# MO_v1.net
KiCad netlist of a schematic drawn in EAGLE
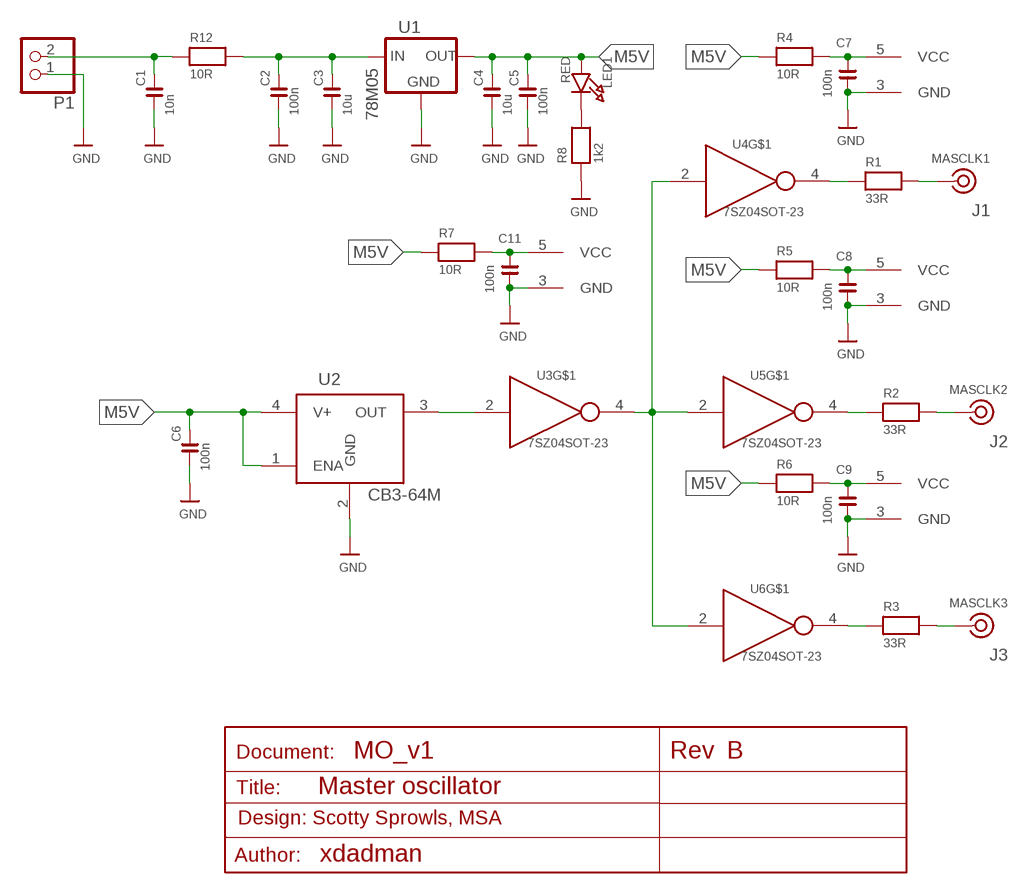
[diagram p0: schematic, sheet 1]

(export (version "E")
  (design (tool "Eeschema 10.0.6"))
  (components
    (comp (ref "C1")
      (value "10n")
      (footprint "eagle-import:C0805")
      (libsource (lib "eagle-import") (part "C080510N"))
    )
    (comp (ref "C2")
      (value "100n")
      (footprint "eagle-import:C0805")
      (libsource (lib "eagle-import") (part "C0805100N"))
    )
    (comp (ref "C3")
      (value "10u")
      (footprint "eagle-import:C1206")
      (libsource (lib "eagle-import") (part "CC120610U"))
    )
    (comp (ref "C4")
      (value "10u")
      (footprint "eagle-import:C1206")
      (libsource (lib "eagle-import") (part "CC120610U"))
    )
    (comp (ref "C5")
      (value "100n")
      (footprint "eagle-import:C0805")
      (libsource (lib "eagle-import") (part "C0805100N"))
    )
    (comp (ref "C6")
      (value "100n")
      (footprint "eagle-import:C0805")
      (libsource (lib "eagle-import") (part "C0805100N"))
    )
    (comp (ref "C7")
      (value "100n")
      (footprint "eagle-import:C0805")
      (libsource (lib "eagle-import") (part "C0805100N"))
    )
    (comp (ref "C8")
      (value "100n")
      (footprint "eagle-import:C0805")
      (libsource (lib "eagle-import") (part "C0805100N"))
    )
    (comp (ref "C9")
      (value "100n")
      (footprint "eagle-import:C0805")
      (libsource (lib "eagle-import") (part "C0805100N"))
    )
    (comp (ref "C11")
      (value "100n")
      (footprint "eagle-import:C0805")
      (libsource (lib "eagle-import") (part "C0805100N"))
    )
    (comp (ref "J1")
      (value "MASCLK1")
      (footprint "eagle-import:SLIM_COAX_PAD")
      (libsource (lib "eagle-import") (part "COAX"))
    )
    (comp (ref "J2")
      (value "MASCLK2")
      (footprint "eagle-import:SLIM_COAX_PAD")
      (libsource (lib "eagle-import") (part "COAX"))
    )
    (comp (ref "J3")
      (value "MASCLK3")
      (footprint "eagle-import:SLIM_COAX_PAD")
      (libsource (lib "eagle-import") (part "COAX"))
    )
    (comp (ref "LED1")
      (value "RED")
      (footprint "eagle-import:CHIPLED_0603")
      (libsource (lib "eagle-import") (part "LED_0603_RED0603"))
    )
    (comp (ref "P1")
      (value "PINHD-1X2")
      (footprint "eagle-import:1X02")
      (libsource (lib "eagle-import") (part "PINHD-1X2"))
    )
    (comp (ref "R1")
      (value "33R")
      (footprint "eagle-import:R0805")
      (libsource (lib "eagle-import") (part "R0805R33"))
    )
    (comp (ref "R2")
      (value "33R")
      (footprint "eagle-import:R0805")
      (libsource (lib "eagle-import") (part "R0805R33"))
    )
    (comp (ref "R3")
      (value "33R")
      (footprint "eagle-import:R0805")
      (libsource (lib "eagle-import") (part "R0805R33"))
    )
    (comp (ref "R4")
      (value "10R")
      (footprint "eagle-import:R0805")
      (libsource (lib "eagle-import") (part "R080510R"))
    )
    (comp (ref "R5")
      (value "10R")
      (footprint "eagle-import:R0805")
      (libsource (lib "eagle-import") (part "R080510R"))
    )
    (comp (ref "R6")
      (value "10R")
      (footprint "eagle-import:R0805")
      (libsource (lib "eagle-import") (part "R080510R"))
    )
    (comp (ref "R7")
      (value "10R")
      (footprint "eagle-import:R0805")
      (libsource (lib "eagle-import") (part "R080510R"))
    )
    (comp (ref "R8")
      (value "1k2")
      (footprint "eagle-import:R0805")
      (libsource (lib "eagle-import") (part "R08051K2"))
    )
    (comp (ref "R12")
      (value "10R")
      (footprint "eagle-import:R0805")
      (libsource (lib "eagle-import") (part "R080510R"))
    )
    (comp (ref "U1")
      (value "78M05")
      (footprint "eagle-import:TO252")
      (libsource (lib "eagle-import") (part "78MXXLDPAK"))
    )
    (comp (ref "U2")
      (value "CB3-64M")
      (footprint "eagle-import:CB3-64M")
      (libsource (lib "eagle-import") (part "CB3-64M"))
    )
    (comp (ref "U3")
      (value "7SZ04SOT-23")
      (footprint "eagle-import:SOT23-5L")
      (libsource (lib "eagle-import") (part "7SZ04SOT-23"))
    )
    (comp (ref "U4")
      (value "7SZ04SOT-23")
      (footprint "eagle-import:SOT23-5L")
      (libsource (lib "eagle-import") (part "7SZ04SOT-23"))
    )
    (comp (ref "U5")
      (value "7SZ04SOT-23")
      (footprint "eagle-import:SOT23-5L")
      (libsource (lib "eagle-import") (part "7SZ04SOT-23"))
    )
    (comp (ref "U6")
      (value "7SZ04SOT-23")
      (footprint "eagle-import:SOT23-5L")
      (libsource (lib "eagle-import") (part "7SZ04SOT-23"))
    )
  )
  (nets
    (net (code "1") (name "GND") (class "Default")
      (node (ref "C1") (pin "1") (pinfunction "1_1") (pintype "passive"))
      (node (ref "C11") (pin "1") (pinfunction "1_1") (pintype "passive"))
      (node (ref "C2") (pin "1") (pinfunction "1_1") (pintype "passive"))
      (node (ref "C3") (pin "1") (pinfunction "1_1") (pintype "passive"))
      (node (ref "C4") (pin "1") (pinfunction "1_1") (pintype "passive"))
      (node (ref "C5") (pin "1") (pinfunction "1_1") (pintype "passive"))
      (node (ref "C6") (pin "1") (pinfunction "1_1") (pintype "passive"))
      (node (ref "C7") (pin "1") (pinfunction "1_1") (pintype "passive"))
      (node (ref "C8") (pin "1") (pinfunction "1_1") (pintype "passive"))
      (node (ref "C9") (pin "1") (pinfunction "1_1") (pintype "passive"))
      (node (ref "P1") (pin "1") (pinfunction "1_1") (pintype "passive"))
      (node (ref "R8") (pin "1") (pinfunction "1_1") (pintype "passive"))
      (node (ref "U1") (pin "3") (pinfunction "GND_3") (pintype "input"))
      (node (ref "U2") (pin "2") (pinfunction "GND_2") (pintype "bidirectional"))
      (node (ref "U3") (pin "3") (pinfunction "GND_3") (pintype "bidirectional"))
      (node (ref "U4") (pin "3") (pinfunction "GND_3") (pintype "bidirectional"))
      (node (ref "U5") (pin "3") (pinfunction "GND_3") (pintype "bidirectional"))
      (node (ref "U6") (pin "3") (pinfunction "GND_3") (pintype "bidirectional"))
    )
    (net (code "2") (name "M5V") (class "Default")
      (node (ref "C4") (pin "2") (pinfunction "2_2") (pintype "passive"))
      (node (ref "C5") (pin "2") (pinfunction "2_2") (pintype "passive"))
      (node (ref "C6") (pin "2") (pinfunction "2_2") (pintype "passive"))
      (node (ref "LED1") (pin "A") (pinfunction "A_A") (pintype "passive"))
      (node (ref "R4") (pin "1") (pinfunction "1_1") (pintype "passive"))
      (node (ref "R5") (pin "1") (pinfunction "1_1") (pintype "passive"))
      (node (ref "R6") (pin "1") (pinfunction "1_1") (pintype "passive"))
      (node (ref "R7") (pin "1") (pinfunction "1_1") (pintype "passive"))
      (node (ref "U1") (pin "2") (pinfunction "OUT_2") (pintype "passive"))
      (node (ref "U2") (pin "1") (pinfunction "ENA_1") (pintype "bidirectional"))
      (node (ref "U2") (pin "4") (pinfunction "V+_4") (pintype "bidirectional"))
    )
    (net (code "3") (name "Net-(C1-Pad2)") (class "Default")
      (node (ref "C1") (pin "2") (pinfunction "2_2") (pintype "passive"))
      (node (ref "P1") (pin "2") (pinfunction "2_2") (pintype "passive"))
      (node (ref "R12") (pin "1") (pinfunction "1_1") (pintype "passive"))
    )
    (net (code "4") (name "Net-(J1A-1)") (class "Default")
      (node (ref "J1") (pin "SIG") (pinfunction "1_SIG") (pintype "passive"))
      (node (ref "R1") (pin "2") (pinfunction "2_2") (pintype "passive"))
    )
    (net (code "5") (name "Net-(J2A-1)") (class "Default")
      (node (ref "J2") (pin "SIG") (pinfunction "1_SIG") (pintype "passive"))
      (node (ref "R2") (pin "2") (pinfunction "2_2") (pintype "passive"))
    )
    (net (code "6") (name "Net-(J3A-1)") (class "Default")
      (node (ref "J3") (pin "SIG") (pinfunction "1_SIG") (pintype "passive"))
      (node (ref "R3") (pin "2") (pinfunction "2_2") (pintype "passive"))
    )
    (net (code "7") (name "Net-(LED1-PadC)") (class "Default")
      (node (ref "LED1") (pin "C") (pinfunction "C_C") (pintype "passive"))
      (node (ref "R8") (pin "2") (pinfunction "2_2") (pintype "passive"))
    )
    (net (code "8") (name "Net-(U1-IN)") (class "Default")
      (node (ref "C2") (pin "2") (pinfunction "2_2") (pintype "passive"))
      (node (ref "C3") (pin "2") (pinfunction "2_2") (pintype "passive"))
      (node (ref "R12") (pin "2") (pinfunction "2_2") (pintype "passive"))
      (node (ref "U1") (pin "1") (pinfunction "IN_1") (pintype "input"))
    )
    (net (code "9") (name "Net-(U2-OUT)") (class "Default")
      (node (ref "U2") (pin "3") (pinfunction "OUT_3") (pintype "bidirectional"))
      (node (ref "U3") (pin "2") (pinfunction "IN_2") (pintype "input"))
    )
    (net (code "10") (name "Net-(U3A-OUT)") (class "Default")
      (node (ref "U3") (pin "4") (pinfunction "OUT_4") (pintype "output"))
      (node (ref "U4") (pin "2") (pinfunction "IN_2") (pintype "input"))
      (node (ref "U5") (pin "2") (pinfunction "IN_2") (pintype "input"))
      (node (ref "U6") (pin "2") (pinfunction "IN_2") (pintype "input"))
    )
    (net (code "11") (name "Net-(U3B-VCC)") (class "Default")
      (node (ref "C11") (pin "2") (pinfunction "2_2") (pintype "passive"))
      (node (ref "R7") (pin "2") (pinfunction "2_2") (pintype "passive"))
      (node (ref "U3") (pin "5") (pinfunction "VCC_5") (pintype "bidirectional"))
    )
    (net (code "12") (name "Net-(U4A-OUT)") (class "Default")
      (node (ref "R1") (pin "1") (pinfunction "1_1") (pintype "passive"))
      (node (ref "U4") (pin "4") (pinfunction "OUT_4") (pintype "output"))
    )
    (net (code "13") (name "Net-(U4B-VCC)") (class "Default")
      (node (ref "C7") (pin "2") (pinfunction "2_2") (pintype "passive"))
      (node (ref "R4") (pin "2") (pinfunction "2_2") (pintype "passive"))
      (node (ref "U4") (pin "5") (pinfunction "VCC_5") (pintype "bidirectional"))
    )
    (net (code "14") (name "Net-(U5A-OUT)") (class "Default")
      (node (ref "R2") (pin "1") (pinfunction "1_1") (pintype "passive"))
      (node (ref "U5") (pin "4") (pinfunction "OUT_4") (pintype "output"))
    )
    (net (code "15") (name "Net-(U5B-VCC)") (class "Default")
      (node (ref "C8") (pin "2") (pinfunction "2_2") (pintype "passive"))
      (node (ref "R5") (pin "2") (pinfunction "2_2") (pintype "passive"))
      (node (ref "U5") (pin "5") (pinfunction "VCC_5") (pintype "bidirectional"))
    )
    (net (code "16") (name "Net-(U6A-OUT)") (class "Default")
      (node (ref "R3") (pin "1") (pinfunction "1_1") (pintype "passive"))
      (node (ref "U6") (pin "4") (pinfunction "OUT_4") (pintype "output"))
    )
    (net (code "17") (name "Net-(U6B-VCC)") (class "Default")
      (node (ref "C9") (pin "2") (pinfunction "2_2") (pintype "passive"))
      (node (ref "R6") (pin "2") (pinfunction "2_2") (pintype "passive"))
      (node (ref "U6") (pin "5") (pinfunction "VCC_5") (pintype "bidirectional"))
    )
  )
)
